# Output.net
KiCad netlist of a schematic drawn in Altium Designer
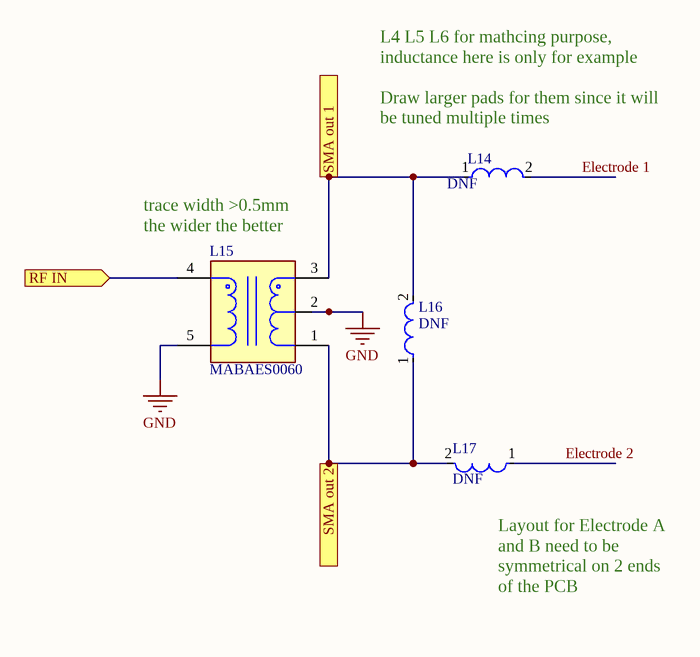
[diagram p0: Output.SchDoc]

(export (version "E")
  (design (tool "Eeschema 10.0.6"))
  (components
    (comp (ref "L14")
      (value "DNF")
      (footprint "FP-MLZ2012-1_25-IPC_C")
      (description "Shielded Multilayer Inductor 1uH ±20% 800mA 130mΩ AEC-Q200 SMD 0805")
      (fields (field (name "TOLERANCE") "20%"))
      (libsource (lib "Altium Content Vault") (part "725321dda6339637d4d059423bc1c3c"))
    )
    (comp (ref "L15")
      (value "MABAES0060")
      (footprint "FP-MABAES0060-MFG")
      (description "BALUN 300KHZ-200MHZ 1:1 6SMD")
      (libsource (lib "Altium Content Vault") (part "a416973d4767a0660ebfda87df8877f"))
    )
    (comp (ref "L16")
      (value "DNF")
      (footprint "FP-MLZ2012-1_25-IPC_C")
      (description "Shielded Multilayer Inductor 1uH ±20% 800mA 130mΩ AEC-Q200 SMD 0805")
      (fields (field (name "TOLERANCE") "20%"))
      (libsource (lib "Altium Content Vault") (part "725321dda6339637d4d059423bc1c3c"))
    )
    (comp (ref "L17")
      (value "DNF")
      (footprint "FP-MLZ2012-1_25-IPC_C")
      (description "Shielded Multilayer Inductor 1uH ±20% 800mA 130mΩ AEC-Q200 SMD 0805")
      (fields (field (name "TOLERANCE") "20%"))
      (libsource (lib "Altium Content Vault") (part "725321dda6339637d4d059423bc1c3c"))
    )
  )
  (nets
    (net (code "1") (name "/Electrode 1") (class "Default")
      (node (ref "L14") (pin "2") (pinfunction "2_2") (pintype "passive"))
    )
    (net (code "2") (name "/Electrode 2") (class "Default")
      (node (ref "L17") (pin "1") (pinfunction "1_1") (pintype "passive"))
    )
    (net (code "3") (name "/RF IN") (class "Default")
      (node (ref "L15") (pin "4") (pinfunction "Primary_dot_4") (pintype "passive"))
    )
    (net (code "4") (name "/SMA out 1") (class "Default")
      (node (ref "L14") (pin "1") (pinfunction "1_1") (pintype "passive"))
      (node (ref "L15") (pin "3") (pinfunction "Secondary_Dot_3") (pintype "passive"))
      (node (ref "L16") (pin "2") (pinfunction "2_2") (pintype "passive"))
    )
    (net (code "5") (name "/SMA out 2") (class "Default")
      (node (ref "L15") (pin "1") (pinfunction "Secondary_1") (pintype "passive"))
      (node (ref "L16") (pin "1") (pinfunction "1_1") (pintype "passive"))
      (node (ref "L17") (pin "2") (pinfunction "2_2") (pintype "passive"))
    )
    (net (code "6") (name "GND") (class "Default")
      (node (ref "L15") (pin "2") (pinfunction "Secondary_CT_2") (pintype "passive"))
      (node (ref "L15") (pin "5") (pinfunction "Primary_5") (pintype "passive"))
    )
  )
)
